# Botdozer_HZ.net
KiCad netlist of a schematic drawn in EAGLE
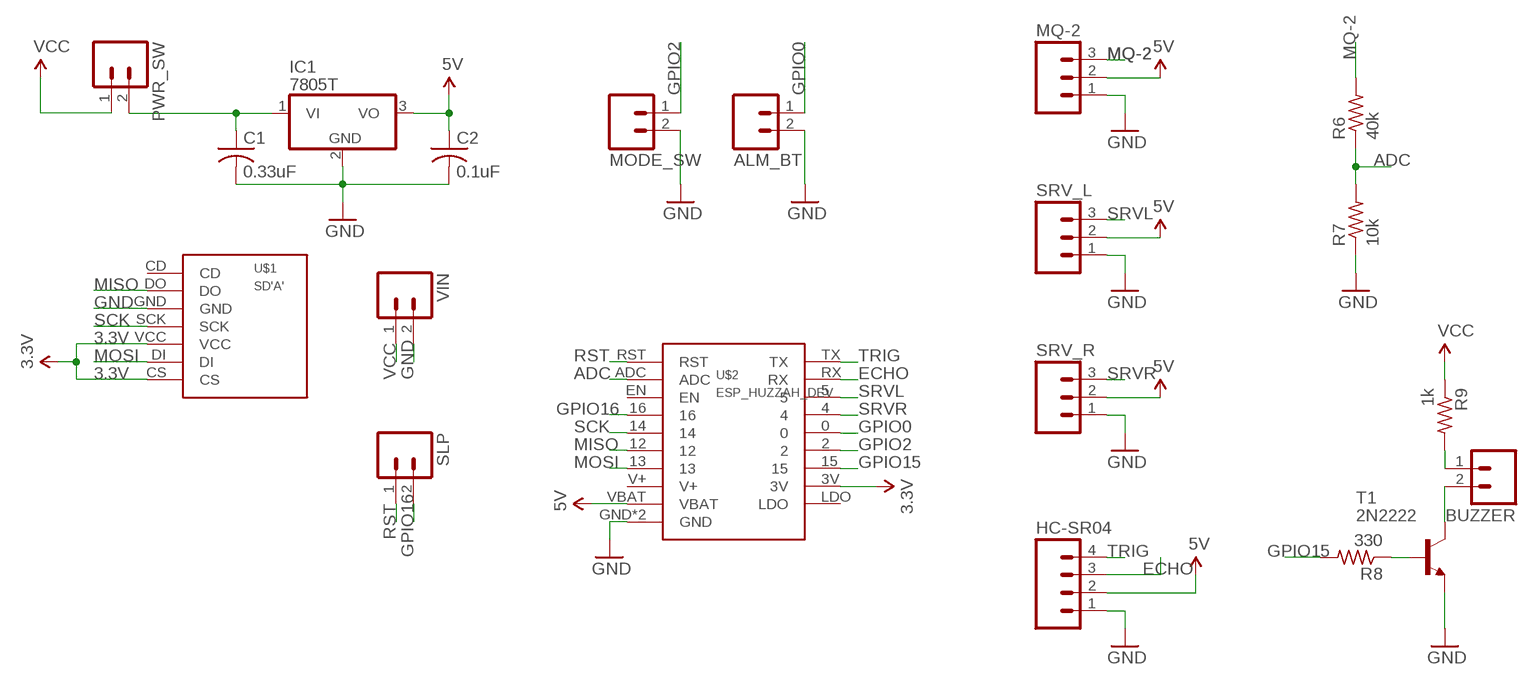
[diagram p0: schematic, sheet 1]

(export (version "E")
  (design (tool "Eeschema 10.0.6"))
  (components
    (comp (ref "ALM_BT")
      (value "M02PTH")
      (footprint "eagle-import:1X02")
      (libsource (lib "eagle-import") (part "M02PTH"))
    )
    (comp (ref "BUZZER")
      (value "M02PTH")
      (footprint "eagle-import:1X02")
      (libsource (lib "eagle-import") (part "M02PTH"))
    )
    (comp (ref "C1")
      (value "0.33uF")
      (footprint "eagle-import:C025-025X050")
      (libsource (lib "eagle-import") (part "C-US025-025X050"))
    )
    (comp (ref "C2")
      (value "0.1uF")
      (footprint "eagle-import:C025-025X050")
      (libsource (lib "eagle-import") (part "C-US025-025X050"))
    )
    (comp (ref "HC-SR04")
      (value "M04PTH")
      (footprint "eagle-import:1X04")
      (libsource (lib "eagle-import") (part "M04PTH"))
    )
    (comp (ref "IC1")
      (value "7805T")
      (footprint "eagle-import:TO220H")
      (libsource (lib "eagle-import") (part "78T05"))
    )
    (comp (ref "MODE_SW")
      (value "M02PTH")
      (footprint "eagle-import:1X02")
      (libsource (lib "eagle-import") (part "M02PTH"))
    )
    (comp (ref "MQ-2")
      (value "M03PTH")
      (footprint "eagle-import:1X03")
      (libsource (lib "eagle-import") (part "M03PTH"))
    )
    (comp (ref "PWR_SW")
      (value "M02PTH")
      (footprint "eagle-import:1X02")
      (libsource (lib "eagle-import") (part "M02PTH"))
    )
    (comp (ref "R6")
      (value "40k")
      (footprint "eagle-import:0207_10")
      (libsource (lib "eagle-import") (part "R-US_0207/10"))
    )
    (comp (ref "R7")
      (value "10k")
      (footprint "eagle-import:0207_10")
      (libsource (lib "eagle-import") (part "R-US_0207/10"))
    )
    (comp (ref "R8")
      (value "330")
      (footprint "eagle-import:0207_10")
      (libsource (lib "eagle-import") (part "R-US_0207/10"))
    )
    (comp (ref "R9")
      (value "1k")
      (footprint "eagle-import:0207_10")
      (libsource (lib "eagle-import") (part "R-US_0207/10"))
    )
    (comp (ref "SLP")
      (value "M02PTH")
      (footprint "eagle-import:1X02")
      (libsource (lib "eagle-import") (part "M02PTH"))
    )
    (comp (ref "SRV_L")
      (value "M03PTH")
      (footprint "eagle-import:1X03")
      (libsource (lib "eagle-import") (part "M03PTH"))
    )
    (comp (ref "SRV_R")
      (value "M03PTH")
      (footprint "eagle-import:1X03")
      (libsource (lib "eagle-import") (part "M03PTH"))
    )
    (comp (ref "T1")
      (value "2N2222")
      (footprint "eagle-import:TO92-EBC-OVAL")
      (libsource (lib "eagle-import") (part "2N2222"))
    )
    (comp (ref "U$1")
      (value "SD'A'")
      (footprint "eagle-import:SD_BR")
      (libsource (lib "eagle-import") (part "SD'A'"))
    )
    (comp (ref "U$2")
      (value "ESP_HUZZAH_DEV")
      (footprint "eagle-import:ESP_HUZZAH_FP")
      (libsource (lib "eagle-import") (part "ESP_HUZZAH_DEV"))
    )
    (comp (ref "VIN")
      (value "M02PTH")
      (footprint "eagle-import:1X02")
      (libsource (lib "eagle-import") (part "M02PTH"))
    )
  )
  (nets
    (net (code "1") (name "/ADC") (class "Default")
      (node (ref "R6") (pin "1") (pinfunction "1_1") (pintype "passive"))
      (node (ref "R7") (pin "2") (pinfunction "2_2") (pintype "passive"))
      (node (ref "U$2") (pin "ADC") (pinfunction "ADC_ADC") (pintype "bidirectional"))
    )
    (net (code "2") (name "/ECHO") (class "Default")
      (node (ref "HC-SR04") (pin "3") (pinfunction "3_3") (pintype "passive"))
      (node (ref "U$2") (pin "RX") (pinfunction "RX_RX") (pintype "bidirectional"))
    )
    (net (code "3") (name "/GPIO0") (class "Default")
      (node (ref "ALM_BT") (pin "1") (pinfunction "1_1") (pintype "passive"))
      (node (ref "U$2") (pin "0") (pinfunction "0_0") (pintype "bidirectional"))
    )
    (net (code "4") (name "/GPIO2") (class "Default")
      (node (ref "MODE_SW") (pin "1") (pinfunction "1_1") (pintype "passive"))
      (node (ref "U$2") (pin "2") (pinfunction "2_2") (pintype "bidirectional"))
    )
    (net (code "5") (name "/GPIO15") (class "Default")
      (node (ref "R8") (pin "2") (pinfunction "2_2") (pintype "passive"))
      (node (ref "U$2") (pin "15") (pinfunction "15_15") (pintype "bidirectional"))
    )
    (net (code "6") (name "/GPIO16") (class "Default")
      (node (ref "SLP") (pin "2") (pinfunction "2_2") (pintype "passive"))
      (node (ref "U$2") (pin "16") (pinfunction "16_16") (pintype "bidirectional"))
    )
    (net (code "7") (name "/MISO") (class "Default")
      (node (ref "U$1") (pin "DO") (pinfunction "DO_DO") (pintype "bidirectional"))
      (node (ref "U$2") (pin "12") (pinfunction "12_12") (pintype "bidirectional"))
    )
    (net (code "8") (name "/MOSI") (class "Default")
      (node (ref "U$1") (pin "DI") (pinfunction "DI_DI") (pintype "bidirectional"))
      (node (ref "U$2") (pin "13") (pinfunction "13_13") (pintype "bidirectional"))
    )
    (net (code "9") (name "/MQ-2") (class "Default")
      (node (ref "MQ-2") (pin "3") (pinfunction "3_3") (pintype "passive"))
      (node (ref "R6") (pin "2") (pinfunction "2_2") (pintype "passive"))
    )
    (net (code "10") (name "/RST") (class "Default")
      (node (ref "SLP") (pin "1") (pinfunction "1_1") (pintype "passive"))
      (node (ref "U$2") (pin "RST") (pinfunction "RST_RST") (pintype "bidirectional"))
    )
    (net (code "11") (name "/SCK") (class "Default")
      (node (ref "U$1") (pin "SCK") (pinfunction "SCK_SCK") (pintype "bidirectional"))
      (node (ref "U$2") (pin "14") (pinfunction "14_14") (pintype "bidirectional"))
    )
    (net (code "12") (name "/SRVL") (class "Default")
      (node (ref "SRV_L") (pin "3") (pinfunction "3_3") (pintype "passive"))
      (node (ref "U$2") (pin "5") (pinfunction "5_5") (pintype "bidirectional"))
    )
    (net (code "13") (name "/SRVR") (class "Default")
      (node (ref "SRV_R") (pin "3") (pinfunction "3_3") (pintype "passive"))
      (node (ref "U$2") (pin "4") (pinfunction "4_4") (pintype "bidirectional"))
    )
    (net (code "14") (name "/TRIG") (class "Default")
      (node (ref "HC-SR04") (pin "4") (pinfunction "4_4") (pintype "passive"))
      (node (ref "U$2") (pin "TX") (pinfunction "TX_TX") (pintype "bidirectional"))
    )
    (net (code "15") (name "3.3V") (class "Default")
      (node (ref "U$1") (pin "CS") (pinfunction "CS_CS") (pintype "bidirectional"))
      (node (ref "U$1") (pin "VCC") (pinfunction "VCC_VCC") (pintype "bidirectional"))
      (node (ref "U$2") (pin "3V") (pinfunction "3V_3V") (pintype "bidirectional"))
    )
    (net (code "16") (name "5V") (class "Default")
      (node (ref "C2") (pin "1") (pinfunction "1_1") (pintype "passive"))
      (node (ref "HC-SR04") (pin "2") (pinfunction "2_2") (pintype "passive"))
      (node (ref "IC1") (pin "3") (pinfunction "VO_3") (pintype "passive"))
      (node (ref "MQ-2") (pin "2") (pinfunction "2_2") (pintype "passive"))
      (node (ref "SRV_L") (pin "2") (pinfunction "2_2") (pintype "passive"))
      (node (ref "SRV_R") (pin "2") (pinfunction "2_2") (pintype "passive"))
      (node (ref "U$2") (pin "VBAT") (pinfunction "VBAT_VBAT") (pintype "bidirectional"))
    )
    (net (code "17") (name "GND") (class "Default")
      (node (ref "ALM_BT") (pin "2") (pinfunction "2_2") (pintype "passive"))
      (node (ref "C1") (pin "2") (pinfunction "2_2") (pintype "passive"))
      (node (ref "C2") (pin "2") (pinfunction "2_2") (pintype "passive"))
      (node (ref "HC-SR04") (pin "1") (pinfunction "1_1") (pintype "passive"))
      (node (ref "IC1") (pin "2") (pinfunction "GND_2") (pintype "passive"))
      (node (ref "MODE_SW") (pin "2") (pinfunction "2_2") (pintype "passive"))
      (node (ref "MQ-2") (pin "1") (pinfunction "1_1") (pintype "passive"))
      (node (ref "R7") (pin "1") (pinfunction "1_1") (pintype "passive"))
      (node (ref "SRV_L") (pin "1") (pinfunction "1_1") (pintype "passive"))
      (node (ref "SRV_R") (pin "1") (pinfunction "1_1") (pintype "passive"))
      (node (ref "T1") (pin "E") (pinfunction "E_E") (pintype "passive"))
      (node (ref "U$1") (pin "GND") (pinfunction "GND_GND") (pintype "bidirectional"))
      (node (ref "U$2") (pin "GND") (pinfunction "GND_GND") (pintype "bidirectional"))
      (node (ref "U$2") (pin "GND1") (pinfunction "GND_GND1") (pintype "bidirectional"))
      (node (ref "VIN") (pin "2") (pinfunction "2_2") (pintype "passive"))
    )
    (net (code "18") (name "Net-(BUZZER-Pad1)") (class "Default")
      (node (ref "BUZZER") (pin "1") (pinfunction "1_1") (pintype "passive"))
      (node (ref "R9") (pin "2") (pinfunction "2_2") (pintype "passive"))
    )
    (net (code "19") (name "Net-(BUZZER-Pad2)") (class "Default")
      (node (ref "BUZZER") (pin "2") (pinfunction "2_2") (pintype "passive"))
      (node (ref "T1") (pin "C") (pinfunction "C_C") (pintype "passive"))
    )
    (net (code "20") (name "Net-(IC1-VI)") (class "Default")
      (node (ref "C1") (pin "1") (pinfunction "1_1") (pintype "passive"))
      (node (ref "IC1") (pin "1") (pinfunction "VI_1") (pintype "input"))
      (node (ref "PWR_SW") (pin "2") (pinfunction "2_2") (pintype "passive"))
    )
    (net (code "21") (name "Net-(R8-Pad1)") (class "Default")
      (node (ref "R8") (pin "1") (pinfunction "1_1") (pintype "passive"))
      (node (ref "T1") (pin "B") (pinfunction "B_B") (pintype "passive"))
    )
    (net (code "22") (name "VCC") (class "Default")
      (node (ref "PWR_SW") (pin "1") (pinfunction "1_1") (pintype "passive"))
      (node (ref "R9") (pin "1") (pinfunction "1_1") (pintype "passive"))
      (node (ref "VIN") (pin "1") (pinfunction "1_1") (pintype "passive"))
    )
    (net (code "23") (name "unconnected-(U$1-PadCD)") (class "Default")
      (node (ref "U$1") (pin "CD") (pinfunction "CD_CD") (pintype "bidirectional"))
    )
    (net (code "24") (name "unconnected-(U$2-PadEN)") (class "Default")
      (node (ref "U$2") (pin "EN") (pinfunction "EN_EN") (pintype "bidirectional"))
    )
    (net (code "25") (name "unconnected-(U$2-PadLDO)") (class "Default")
      (node (ref "U$2") (pin "LDO") (pinfunction "LDO_LDO") (pintype "bidirectional"))
    )
    (net (code "26") (name "unconnected-(U$2-PadV+)") (class "Default")
      (node (ref "U$2") (pin "V+") (pinfunction "V+_V+") (pintype "bidirectional"))
    )
  )
)
